# psas_c3_team05.net
KiCad netlist of a schematic drawn in EAGLE
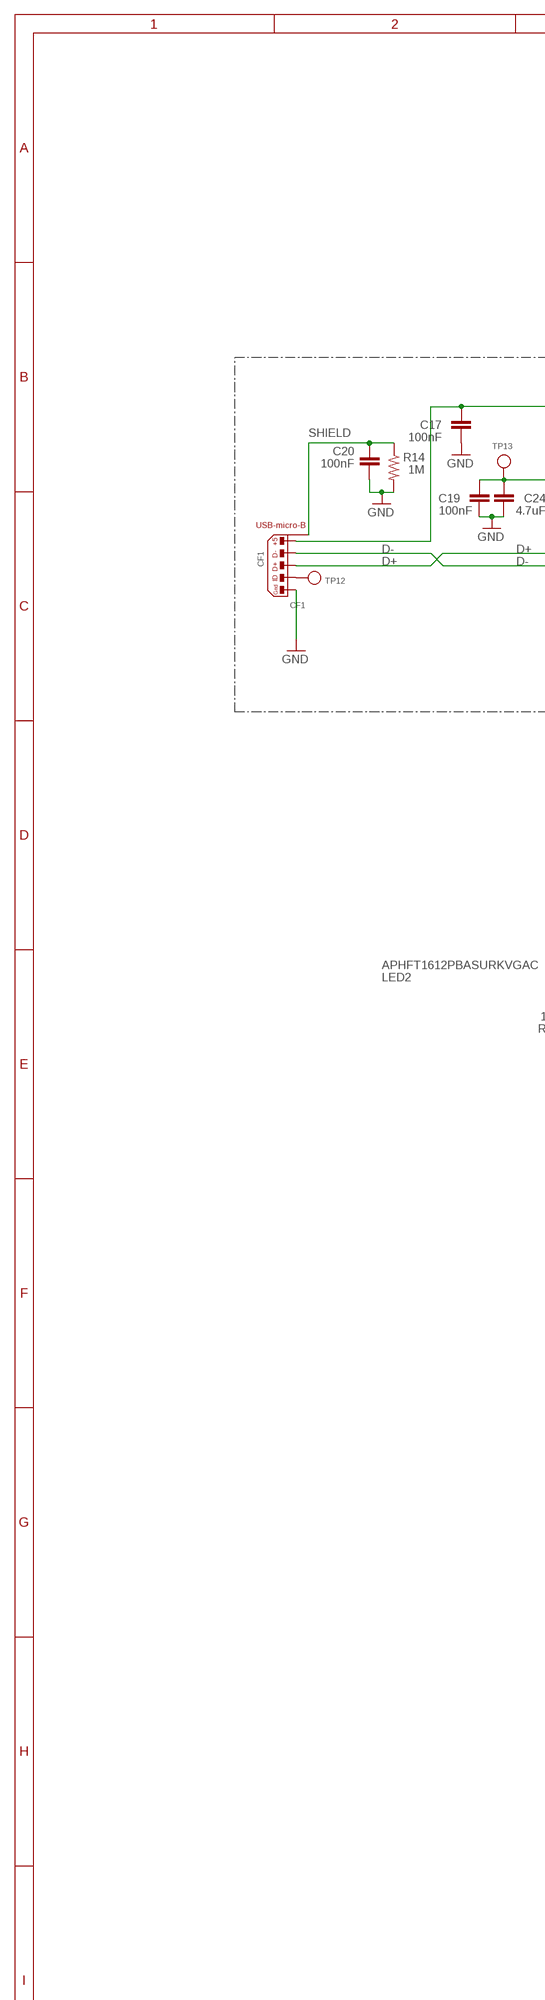
[diagram p0: schematic, sheet 1, part 1 of 2]
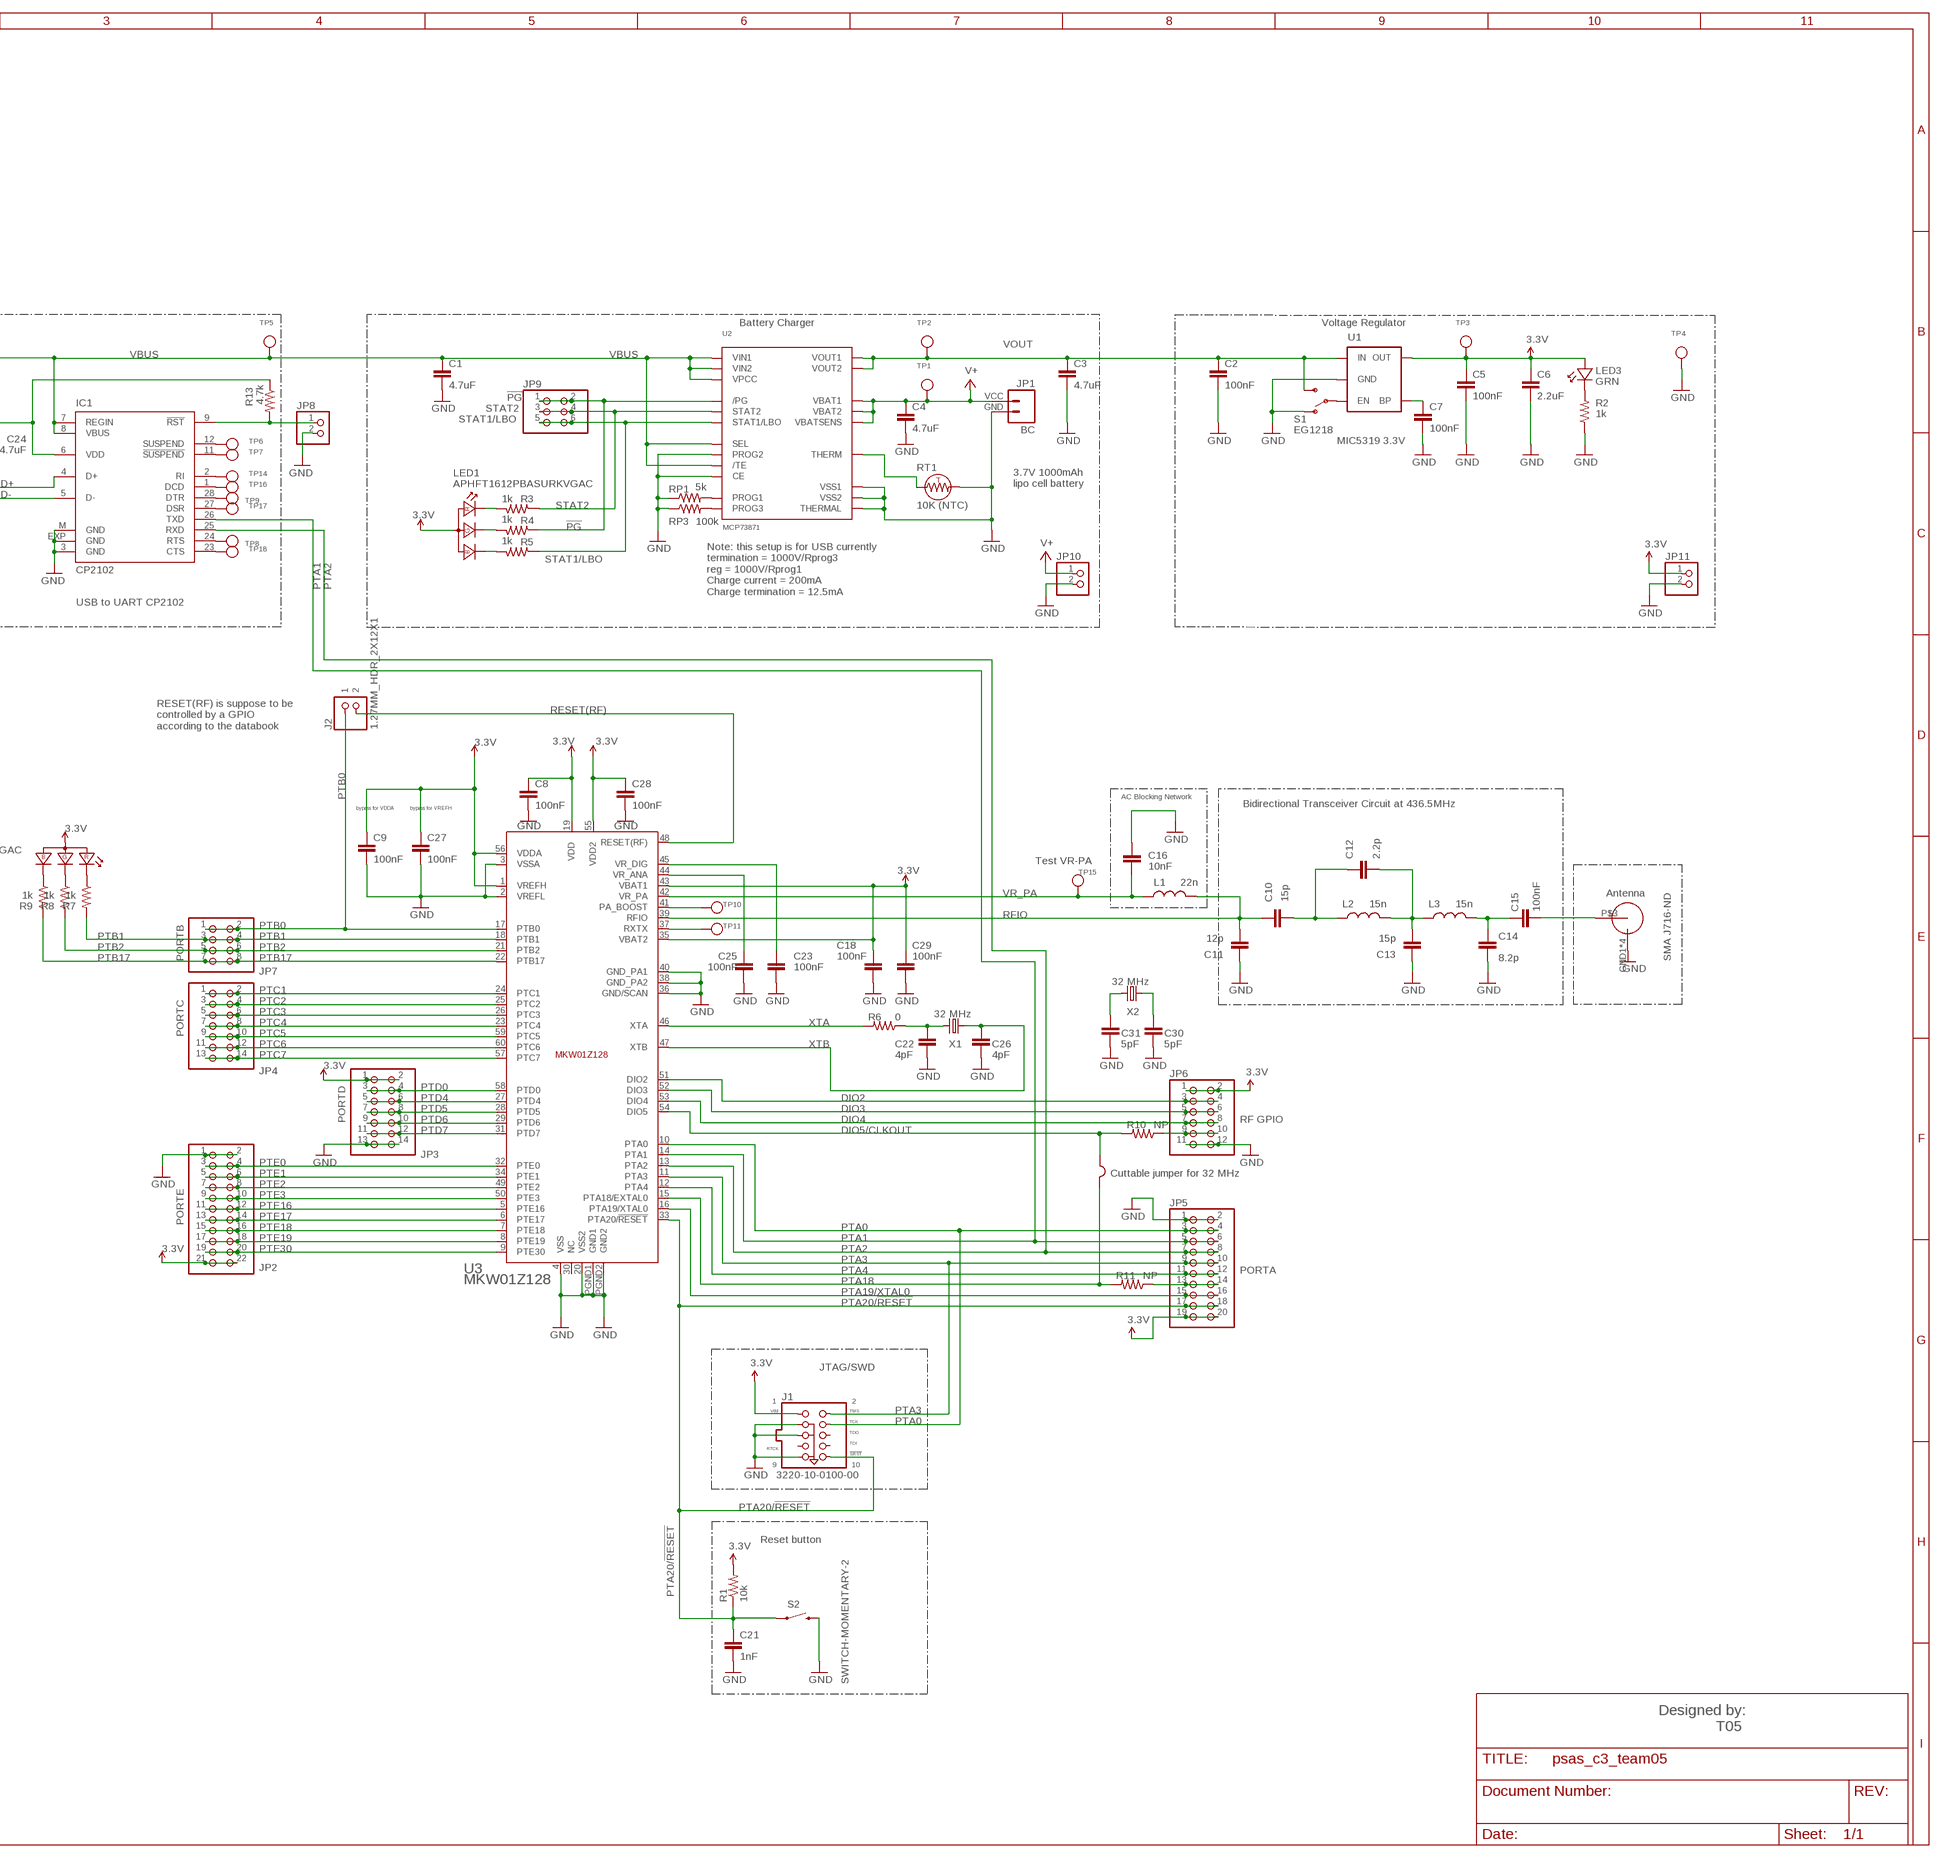
[diagram p1: schematic, sheet 1, part 2 of 2]

(export (version "E")
  (design (tool "Eeschema 10.0.6"))
  (components
    (comp (ref "C1")
      (value "4.7uF")
      (footprint "eagle-import:.0805-B-NOSILK")
      (fields (field (name "MFG") "Wurth Electronics Inc"))
      (libsource (lib "eagle-import") (part "rcl_custom_C-EU0805-B-NOSILK"))
    )
    (comp (ref "C2")
      (value "100nF")
      (footprint "eagle-import:.0603-B-NOSILK")
      (fields (field (name "MFG") "Murata Electronics North America"))
      (libsource (lib "eagle-import") (part "rcl_custom_C-EU0603-B-NOSILK"))
    )
    (comp (ref "C3")
      (value "4.7uF")
      (footprint "eagle-import:.0805-B-NOSILK")
      (fields (field (name "MFG") "Wurth Electronics Inc"))
      (libsource (lib "eagle-import") (part "rcl_custom_C-EU0805-B-NOSILK"))
    )
    (comp (ref "C4")
      (value "4.7uF")
      (footprint "eagle-import:.0805-B-NOSILK")
      (fields (field (name "MFG") "Wurth Electronics Inc"))
      (libsource (lib "eagle-import") (part "rcl_custom_C-EU0805-B-NOSILK"))
    )
    (comp (ref "C5")
      (value "100nF")
      (footprint "eagle-import:.0603-B-NOSILK")
      (fields (field (name "MFG") "Murata Electronics North America"))
      (libsource (lib "eagle-import") (part "rcl_custom_C-EU0603-B-NOSILK"))
    )
    (comp (ref "C6")
      (value "2.2uF")
      (footprint "eagle-import:.0805-B-NOSILK")
      (fields (field (name "MFG") "Murata Electronics North America"))
      (libsource (lib "eagle-import") (part "rcl_custom_C-EU0805-B-NOSILK"))
    )
    (comp (ref "C7")
      (value "100nF")
      (footprint "eagle-import:.0603-B-NOSILK")
      (fields (field (name "MFG") "Murata Electronics North America"))
      (libsource (lib "eagle-import") (part "rcl_custom_C-EU0603-B-NOSILK"))
    )
    (comp (ref "C8")
      (value "100nF")
      (footprint "eagle-import:.0603-B-NOSILK")
      (fields
        (field (name "MFG") "Murata Electronics North America")
        (field (name "MPN") "GRM188R71C104KA01D")
      )
      (libsource (lib "eagle-import") (part "C-EU0603-B-NOSILK"))
    )
    (comp (ref "C9")
      (value "100nF")
      (footprint "eagle-import:.0603-B-NOSILK")
      (fields
        (field (name "MFG") "Murata Electronics North America")
        (field (name "MPN") "GRM188R71C104KA01D")
      )
      (libsource (lib "eagle-import") (part "C-EU0603-B-NOSILK"))
    )
    (comp (ref "C10")
      (value "15p")
      (footprint "eagle-import:.0603-B-NOSILK")
      (fields (field (name "MFG") "AVX"))
      (libsource (lib "eagle-import") (part "rcl_custom_C-EU0603-B-NOSILK"))
    )
    (comp (ref "C11")
      (value "12p")
      (footprint "eagle-import:.0603-B-NOSILK")
      (fields (field (name "MFG") "AVX"))
      (libsource (lib "eagle-import") (part "rcl_custom_C-EU0603-B-NOSILK"))
    )
    (comp (ref "C12")
      (value "2.2p")
      (footprint "eagle-import:.0603-B-NOSILK")
      (fields (field (name "MFG") "Vishay / Vitramon"))
      (libsource (lib "eagle-import") (part "rcl_custom_C-EU0603-B-NOSILK"))
    )
    (comp (ref "C13")
      (value "15p")
      (footprint "eagle-import:.0603-B-NOSILK")
      (fields (field (name "MFG") "AVX"))
      (libsource (lib "eagle-import") (part "rcl_custom_C-EU0603-B-NOSILK"))
    )
    (comp (ref "C14")
      (value "8.2p")
      (footprint "eagle-import:.0603-B-NOSILK")
      (fields (field (name "MFG") "Johanson Technology"))
      (libsource (lib "eagle-import") (part "rcl_custom_C-EU0603-B-NOSILK"))
    )
    (comp (ref "C15")
      (value "100nF")
      (footprint "eagle-import:.0603-B-NOSILK")
      (fields (field (name "MFG") "AVX"))
      (libsource (lib "eagle-import") (part "rcl_custom_C-EU0603-B-NOSILK"))
    )
    (comp (ref "C16")
      (value "10nF")
      (footprint "eagle-import:.0603-B-NOSILK")
      (fields (field (name "MFG") "AVX"))
      (libsource (lib "eagle-import") (part "rcl_custom_C-EU0603-B-NOSILK"))
    )
    (comp (ref "C17")
      (value "100nF")
      (footprint "eagle-import:.0603-B-NOSILK")
      (fields (field (name "MFG") "Murata Electronics North America"))
      (libsource (lib "eagle-import") (part "rcl_custom_C-EU0603-B-NOSILK"))
    )
    (comp (ref "C18")
      (value "100nF")
      (footprint "eagle-import:.0603-B-NOSILK")
      (fields
        (field (name "MFG") "Murata Electronics North America")
        (field (name "MPN") "GRM188R71C104KA01D")
      )
      (libsource (lib "eagle-import") (part "C-EU0603-B-NOSILK"))
    )
    (comp (ref "C19")
      (value "100nF")
      (footprint "eagle-import:.0603-B-NOSILK")
      (fields (field (name "MFG") "Murata Electronics North America"))
      (libsource (lib "eagle-import") (part "rcl_custom_C-EU0603-B-NOSILK"))
    )
    (comp (ref "C20")
      (value "100nF")
      (footprint "eagle-import:.0603-B-NOSILK")
      (fields (field (name "MFG") "Murata Electronics North America"))
      (libsource (lib "eagle-import") (part "rcl_custom_C-EU0603-B-NOSILK"))
    )
    (comp (ref "C21")
      (value "1nF")
      (footprint "eagle-import:.0603-B-NOSILK")
      (fields (field (name "MFG") "Kemet"))
      (libsource (lib "eagle-import") (part "rcl_custom_C-EU0603-B-NOSILK"))
    )
    (comp (ref "C22")
      (value "4pF")
      (footprint "eagle-import:.0603-B-NOSILK")
      (fields
        (field (name "MFG") "Murata Electronics North America")
        (field (name "MPN") "GRM1885C1H4R0CA01D")
      )
      (libsource (lib "eagle-import") (part "C-EU0603-B-NOSILK"))
    )
    (comp (ref "C23")
      (value "100nF")
      (footprint "eagle-import:.0603-B-NOSILK")
      (fields
        (field (name "MFG") "Murata Electronics North America")
        (field (name "MPN") "GRM188R71C104KA01D")
      )
      (libsource (lib "eagle-import") (part "C-EU0603-B-NOSILK"))
    )
    (comp (ref "C24")
      (value "4.7uF")
      (footprint "eagle-import:.0805-B-NOSILK")
      (fields (field (name "MFG") "Wurth Electronics Inc"))
      (libsource (lib "eagle-import") (part "rcl_custom_C-EU0805-B-NOSILK"))
    )
    (comp (ref "C25")
      (value "100nF")
      (footprint "eagle-import:.0603-B-NOSILK")
      (fields
        (field (name "MFG") "Murata Electronics North America")
        (field (name "MPN") "GRM188R71C104KA01D")
      )
      (libsource (lib "eagle-import") (part "C-EU0603-B-NOSILK"))
    )
    (comp (ref "C26")
      (value "4pF")
      (footprint "eagle-import:.0603-B-NOSILK")
      (fields
        (field (name "MFG") "Murata Electronics North America")
        (field (name "MPN") "GRM1885C1H4R0CA01D")
      )
      (libsource (lib "eagle-import") (part "C-EU0603-B-NOSILK"))
    )
    (comp (ref "C27")
      (value "100nF")
      (footprint "eagle-import:.0603-B-NOSILK")
      (fields
        (field (name "MFG") "Murata Electronics North America")
        (field (name "MPN") "GRM188R71C104KA01D")
      )
      (libsource (lib "eagle-import") (part "C-EU0603-B-NOSILK"))
    )
    (comp (ref "C28")
      (value "100nF")
      (footprint "eagle-import:.0603-B-NOSILK")
      (fields
        (field (name "MFG") "Murata Electronics North America")
        (field (name "MPN") "GRM188R71C104KA01D")
      )
      (libsource (lib "eagle-import") (part "C-EU0603-B-NOSILK"))
    )
    (comp (ref "C29")
      (value "100nF")
      (footprint "eagle-import:.0603-B-NOSILK")
      (fields
        (field (name "MFG") "Murata Electronics North America")
        (field (name "MPN") "GRM188R71C104KA01D")
      )
      (libsource (lib "eagle-import") (part "C-EU0603-B-NOSILK"))
    )
    (comp (ref "C30")
      (value "5pF")
      (footprint "eagle-import:.0603-B-NOSILK")
      (fields
        (field (name "MFG") "Murata Electronics North America")
        (field (name "MPN") "GRM1885C1H4R0CA01D")
      )
      (libsource (lib "eagle-import") (part "C-EU0603-B-NOSILK"))
    )
    (comp (ref "C31")
      (value "5pF")
      (footprint "eagle-import:.0603-B-NOSILK")
      (fields
        (field (name "MFG") "Murata Electronics North America")
        (field (name "MPN") "GRM1885C1H4R0CA01D")
      )
      (libsource (lib "eagle-import") (part "C-EU0603-B-NOSILK"))
    )
    (comp (ref "CF1")
      (value "CF1")
      (footprint "eagle-import:USB-MICRO-B-PTH-HIROSE")
      (fields (field (name "MFG") "Hirose Electric Co Ltd"))
      (libsource (lib "eagle-import") (part "CON_USB-MICRO-B-RECEPTACLE-PTH-HIROSE-ZX62D-B-5P8"))
    )
    (comp (ref "IC1")
      (value "CP2102")
      (footprint "eagle-import:MLP28")
      (fields
        (field (name "MF") "FARNELL")
        (field (name "MPN") "CP2102-GM")
        (field (name "MFG") "Silicon Labs")
      )
      (libsource (lib "eagle-import") (part "CP2102"))
    )
    (comp (ref "J1")
      (value "3220-10-0100-00")
      (footprint "eagle-import:PINHEADER-2X5-0.05+POL+SILK")
      (fields (field (name "MFG") "CNC Tech"))
      (libsource (lib "eagle-import") (part "JTAG_ARM-10-50MIL"))
    )
    (comp (ref "J2")
      (value "1.27MM_HDR_2X12X1")
      (footprint "eagle-import:1.27MM_2X1")
      (libsource (lib "eagle-import") (part "1.27MM_HDR_2X12X1"))
    )
    (comp (ref "JP1")
      (value "BC")
      (footprint "eagle-import:SPARKFUN-CONNECTORS_JST-2-SMD-VERT")
      (fields (field (name "MFG") "JST Sales America Inc."))
      (libsource (lib "eagle-import") (part "SPARKFUN-CONNECTORS_M024UCON-15767"))
    )
    (comp (ref "JP2")
      (value "PINHD-2X11")
      (footprint "eagle-import:2X11")
      (libsource (lib "eagle-import") (part "PINHD-2X11"))
    )
    (comp (ref "JP3")
      (value "PINHD-2X7")
      (footprint "eagle-import:2X07")
      (libsource (lib "eagle-import") (part "PINHD-2X7"))
    )
    (comp (ref "JP4")
      (value "PINHD-2X7")
      (footprint "eagle-import:2X07")
      (libsource (lib "eagle-import") (part "PINHD-2X7"))
    )
    (comp (ref "JP5")
      (value "PINHD-2X10")
      (footprint "eagle-import:2X10")
      (libsource (lib "eagle-import") (part "PINHD-2X10"))
    )
    (comp (ref "JP6")
      (value "PINHD-2X6")
      (footprint "eagle-import:2X06")
      (libsource (lib "eagle-import") (part "PINHD-2X6"))
    )
    (comp (ref "JP7")
      (value "PINHD-2X4")
      (footprint "eagle-import:2X04")
      (libsource (lib "eagle-import") (part "PINHD-2X4"))
    )
    (comp (ref "JP8")
      (value "PINHD-1X2")
      (footprint "eagle-import:1X02")
      (libsource (lib "eagle-import") (part "PINHD-1X2"))
    )
    (comp (ref "JP9")
      (value "PINHD-2X3")
      (footprint "eagle-import:2X03")
      (libsource (lib "eagle-import") (part "PINHD-2X3"))
    )
    (comp (ref "JP10")
      (value "PINHD-1X2")
      (footprint "eagle-import:1X02")
      (libsource (lib "eagle-import") (part "PINHD-1X2"))
    )
    (comp (ref "JP11")
      (value "PINHD-1X2")
      (footprint "eagle-import:1X02")
      (libsource (lib "eagle-import") (part "PINHD-1X2"))
    )
    (comp (ref "L1")
      (value "22n")
      (footprint "eagle-import:.0603-B-NOSILK")
      (fields (field (name "MFG") "Murata"))
      (libsource (lib "eagle-import") (part "L-US0603-B-NOSILK"))
    )
    (comp (ref "L2")
      (value "15n")
      (footprint "eagle-import:.0603-B-NOSILK")
      (fields (field (name "MFG") "Murata"))
      (libsource (lib "eagle-import") (part "L-US0603-B-NOSILK"))
    )
    (comp (ref "L3")
      (value "15n")
      (footprint "eagle-import:.0603-B-NOSILK")
      (fields (field (name "MFG") "Murata"))
      (libsource (lib "eagle-import") (part "L-US0603-B-NOSILK"))
    )
    (comp (ref "LED1")
      (value "APHFT1612PBASURKVGAC")
      (footprint "eagle-import:KINGBRITE_RGBLED_1.6X1.26")
      (fields (field (name "MFG") "Lite-On Inc."))
      (libsource (lib "eagle-import") (part "LED_RGB_COMMON_ANODE-1.6X1.26"))
    )
    (comp (ref "LED2")
      (value "APHFT1612PBASURKVGAC")
      (footprint "eagle-import:KINGBRITE_RGBLED_1.6X1.26")
      (fields (field (name "MFG") "Lite-On Inc."))
      (libsource (lib "eagle-import") (part "LED_RGB_COMMON_ANODE-1.6X1.26"))
    )
    (comp (ref "LED3")
      (value "GRN")
      (footprint "eagle-import:LED-0603")
      (fields (field (name "MFG") "Lite-On Inc."))
      (libsource (lib "eagle-import") (part "LED-0603"))
    )
    (comp (ref "R1")
      (value "10k")
      (footprint "eagle-import:.0603-B-NOSILK")
      (fields (field (name "MFG") "Yageo"))
      (libsource (lib "eagle-import") (part "R-US_0603-B-NOSILK"))
    )
    (comp (ref "R2")
      (value "1k")
      (footprint "eagle-import:.0603-B-NOSILK")
      (fields (field (name "MFG") "Yageo"))
      (libsource (lib "eagle-import") (part "R-US_0603-B-NOSILK"))
    )
    (comp (ref "R3")
      (value "1k")
      (footprint "eagle-import:.0603-B-NOSILK")
      (fields (field (name "MFG") "Yageo"))
      (libsource (lib "eagle-import") (part "R-US_0603-B-NOSILK"))
    )
    (comp (ref "R4")
      (value "1k")
      (footprint "eagle-import:.0603-B-NOSILK")
      (fields (field (name "MFG") "Yageo"))
      (libsource (lib "eagle-import") (part "R-US_0603-B-NOSILK"))
    )
    (comp (ref "R5")
      (value "1k")
      (footprint "eagle-import:.0603-B-NOSILK")
      (fields (field (name "MFG") "Yageo"))
      (libsource (lib "eagle-import") (part "R-US_0603-B-NOSILK"))
    )
    (comp (ref "R6")
      (value "0")
      (footprint "eagle-import:.0603-B-NOSILK")
      (libsource (lib "eagle-import") (part "R-US_0603-B-NOSILK"))
    )
    (comp (ref "R7")
      (value "1k")
      (footprint "eagle-import:.0603-B-NOSILK")
      (fields (field (name "MFG") "Yageo"))
      (libsource (lib "eagle-import") (part "R-US_0603-B-NOSILK"))
    )
    (comp (ref "R8")
      (value "1k")
      (footprint "eagle-import:.0603-B-NOSILK")
      (fields (field (name "MFG") "Yageo"))
      (libsource (lib "eagle-import") (part "R-US_0603-B-NOSILK"))
    )
    (comp (ref "R9")
      (value "1k")
      (footprint "eagle-import:.0603-B-NOSILK")
      (fields (field (name "MFG") "Yageo"))
      (libsource (lib "eagle-import") (part "R-US_0603-B-NOSILK"))
    )
    (comp (ref "R10")
      (value "NP")
      (footprint "eagle-import:.0603-B-NOSILK")
      (libsource (lib "eagle-import") (part "R-US_0603-B-NOSILK"))
    )
    (comp (ref "R11")
      (value "NP")
      (footprint "eagle-import:.0603-B-NOSILK")
      (libsource (lib "eagle-import") (part "R-US_0603-B-NOSILK"))
    )
    (comp (ref "R13")
      (value "4.7k")
      (footprint "eagle-import:.0603-B-NOSILK")
      (fields (field (name "MFG") "Yageo"))
      (libsource (lib "eagle-import") (part "R-US_0603-B-NOSILK"))
    )
    (comp (ref "R14")
      (value "1M")
      (footprint "eagle-import:.0603-B-NOSILK")
      (fields (field (name "MFG") "Yageo"))
      (libsource (lib "eagle-import") (part "R-US_0603-B-NOSILK"))
    )
    (comp (ref "RP1")
      (value "5k")
      (footprint "eagle-import:.0603-B-NOSILK")
      (fields (field (name "MFG") "Yageo"))
      (libsource (lib "eagle-import") (part "R-US_0603-B-NOSILK"))
    )
    (comp (ref "RP3")
      (value "100k")
      (footprint "eagle-import:.0603-B-NOSILK")
      (fields (field (name "MFG") "Yageo"))
      (libsource (lib "eagle-import") (part "R-US_0603-B-NOSILK"))
    )
    (comp (ref "RT1")
      (value "10K (NTC)")
      (footprint "eagle-import:R1206")
      (fields (field (name "MFG") "Honeywell Sensing and Control"))
      (libsource (lib "eagle-import") (part "THERMISTOR-_1206"))
    )
    (comp (ref "S1")
      (value "EG1218")
      (footprint "eagle-import:SWITCH-SPDT")
      (fields (field (name "MFG") "E-Switch"))
      (libsource (lib "eagle-import") (part "SWITCH-SPSTPTH"))
    )
    (comp (ref "S2")
      (value "SWITCH-MOMENTARY-2")
      (footprint "eagle-import:TACTILE_SWITCH_TALL")
      (fields (field (name "MFG") "TE Connectivity Alcoswitch Switches"))
      (libsource (lib "eagle-import") (part "SWITCH-MOMENTARY-2"))
    )
    (comp (ref "TP1")
      (value "TESTPOINTROUND0.5MM")
      (footprint "eagle-import:TESTPOINT_ROUND_0.5MM")
      (libsource (lib "eagle-import") (part "TESTPOINTROUND0.5MM"))
    )
    (comp (ref "TP2")
      (value "TESTPOINTROUND0.5MM")
      (footprint "eagle-import:TESTPOINT_ROUND_0.5MM")
      (libsource (lib "eagle-import") (part "TESTPOINTROUND0.5MM"))
    )
    (comp (ref "TP3")
      (value "TESTPOINTROUND0.5MM")
      (footprint "eagle-import:TESTPOINT_ROUND_0.5MM")
      (libsource (lib "eagle-import") (part "TESTPOINTROUND0.5MM"))
    )
    (comp (ref "TP4")
      (value "TESTPOINTROUND0.5MM")
      (footprint "eagle-import:TESTPOINT_ROUND_0.5MM")
      (libsource (lib "eagle-import") (part "TESTPOINTROUND0.5MM"))
    )
    (comp (ref "TP5")
      (value "TESTPOINTROUND0.5MM")
      (footprint "eagle-import:TESTPOINT_ROUND_0.5MM")
      (libsource (lib "eagle-import") (part "TESTPOINTROUND0.5MM"))
    )
    (comp (ref "TP6")
      (value "TESTPOINTROUND0.5MM")
      (footprint "eagle-import:TESTPOINT_ROUND_0.5MM")
      (libsource (lib "eagle-import") (part "TESTPOINTROUND0.5MM"))
    )
    (comp (ref "TP7")
      (value "TESTPOINTROUND0.5MM")
      (footprint "eagle-import:TESTPOINT_ROUND_0.5MM")
      (libsource (lib "eagle-import") (part "TESTPOINTROUND0.5MM"))
    )
    (comp (ref "TP8")
      (value "TESTPOINTROUND0.5MM")
      (footprint "eagle-import:TESTPOINT_ROUND_0.5MM")
      (libsource (lib "eagle-import") (part "TESTPOINTROUND0.5MM"))
    )
    (comp (ref "TP9")
      (value "TESTPOINTROUND0.5MM")
      (footprint "eagle-import:TESTPOINT_ROUND_0.5MM")
      (libsource (lib "eagle-import") (part "TESTPOINTROUND0.5MM"))
    )
    (comp (ref "TP10")
      (value "TESTPOINTROUND0.5MM")
      (footprint "eagle-import:TESTPOINT_ROUND_0.5MM")
      (libsource (lib "eagle-import") (part "TESTPOINTROUND0.5MM"))
    )
    (comp (ref "TP11")
      (value "TESTPOINTROUND0.5MM")
      (footprint "eagle-import:TESTPOINT_ROUND_0.5MM")
      (libsource (lib "eagle-import") (part "TESTPOINTROUND0.5MM"))
    )
    (comp (ref "TP12")
      (value "TESTPOINTROUND0.5MM")
      (footprint "eagle-import:TESTPOINT_ROUND_0.5MM")
      (libsource (lib "eagle-import") (part "TESTPOINTROUND0.5MM"))
    )
    (comp (ref "TP13")
      (value "TESTPOINTROUND0.5MM")
      (footprint "eagle-import:TESTPOINT_ROUND_0.5MM")
      (libsource (lib "eagle-import") (part "TESTPOINTROUND0.5MM"))
    )
    (comp (ref "TP14")
      (value "TESTPOINTROUND0.5MM")
      (footprint "eagle-import:TESTPOINT_ROUND_0.5MM")
      (libsource (lib "eagle-import") (part "TESTPOINTROUND0.5MM"))
    )
    (comp (ref "TP15")
      (value "TESTPOINTROUND0.5MM")
      (footprint "eagle-import:TESTPOINT_ROUND_0.5MM")
      (libsource (lib "eagle-import") (part "TESTPOINTROUND0.5MM"))
    )
    (comp (ref "TP16")
      (value "TESTPOINTROUND0.5MM")
      (footprint "eagle-import:TESTPOINT_ROUND_0.5MM")
      (libsource (lib "eagle-import") (part "TESTPOINTROUND0.5MM"))
    )
    (comp (ref "TP17")
      (value "TESTPOINTROUND0.5MM")
      (footprint "eagle-import:TESTPOINT_ROUND_0.5MM")
      (libsource (lib "eagle-import") (part "TESTPOINTROUND0.5MM"))
    )
    (comp (ref "TP18")
      (value "TESTPOINTROUND0.5MM")
      (footprint "eagle-import:TESTPOINT_ROUND_0.5MM")
      (libsource (lib "eagle-import") (part "TESTPOINTROUND0.5MM"))
    )
    (comp (ref "U$2")
      (value "SMAJ716-ND")
      (footprint "eagle-import:SMAJ716-ND")
      (fields (field (name "MFG") "Cinch Connectivity Solutions"))
      (libsource (lib "eagle-import") (part "SMAJ716-ND"))
    )
    (comp (ref "U1")
      (value "MIC5319 3.3V")
      (footprint "eagle-import:SPARKFUN-POWERIC_SOT23-5")
      (fields (field (name "MFG") "Microchip Technology"))
      (libsource (lib "eagle-import") (part "SPARKFUN-POWERIC_V_REG_MIC52193.3V"))
    )
    (comp (ref "U2")
      (value "MCP73871")
      (footprint "eagle-import:QFN20_4MM")
      (fields (field (name "MFG") "Microchip Technology"))
      (libsource (lib "eagle-import") (part "MCP73871"))
    )
    (comp (ref "U3")
      (value "MKW01Z128")
      (footprint "eagle-import:MKW01Z128")
      (fields (field (name "MFG") "Freescale Semiconductor"))
      (libsource (lib "eagle-import") (part "MKW01Z128"))
    )
    (comp (ref "W1")
      (value "CONNECTION-0.4")
      (footprint "eagle-import:CONNECTION-BUTT-0.4")
      (libsource (lib "eagle-import") (part "CONNECTION-0.4"))
    )
    (comp (ref "X1")
      (value "32 MHz")
      (footprint "eagle-import:FC-12M")
      (fields (field (name "MFG") "AVX Corp/Kyocera Corp"))
      (libsource (lib "eagle-import") (part "FC-12M"))
    )
    (comp (ref "X2")
      (value "32 MHz")
      (footprint "eagle-import:FC-12M")
      (fields (field (name "MFG") "CTS-Frequency Controls"))
      (libsource (lib "eagle-import") (part "FC-12M"))
    )
  )
  (nets
    (net (code "1") (name "/D+") (class "Default")
      (node (ref "CF1") (pin "3") (pinfunction "3_3") (pintype "passive"))
      (node (ref "IC1") (pin "4") (pinfunction "D+_4") (pintype "bidirectional"))
    )
    (net (code "2") (name "/D-") (class "Default")
      (node (ref "CF1") (pin "2") (pinfunction "2_2") (pintype "passive"))
      (node (ref "IC1") (pin "5") (pinfunction "D-_5") (pintype "bidirectional"))
    )
    (net (code "3") (name "/DIO2") (class "Default")
      (node (ref "JP6") (pin "3") (pinfunction "3_3") (pintype "passive"))
      (node (ref "JP6") (pin "4") (pinfunction "4_4") (pintype "passive"))
      (node (ref "U3") (pin "51") (pinfunction "DIO2_51") (pintype "bidirectional"))
    )
    (net (code "4") (name "/DIO3") (class "Default")
      (node (ref "JP6") (pin "5") (pinfunction "5_5") (pintype "passive"))
      (node (ref "JP6") (pin "6") (pinfunction "6_6") (pintype "passive"))
      (node (ref "U3") (pin "52") (pinfunction "DIO3_52") (pintype "bidirectional"))
    )
    (net (code "5") (name "/DIO4") (class "Default")
      (node (ref "JP6") (pin "7") (pinfunction "7_7") (pintype "passive"))
      (node (ref "JP6") (pin "8") (pinfunction "8_8") (pintype "passive"))
      (node (ref "U3") (pin "53") (pinfunction "DIO4_53") (pintype "bidirectional"))
    )
    (net (code "6") (name "/DIO5{slash}CLKOUT") (class "Default")
      (node (ref "R10") (pin "2") (pinfunction "2_2") (pintype "passive"))
      (node (ref "U3") (pin "54") (pinfunction "DIO5_54") (pintype "bidirectional"))
      (node (ref "W1") (pin "P1") (pinfunction "1_P1") (pintype "passive"))
    )
    (net (code "7") (name "/PTA0") (class "Default")
      (node (ref "J1") (pin "4") (pinfunction "TCK_4") (pintype "passive"))
      (node (ref "JP5") (pin "3") (pinfunction "3_3") (pintype "passive"))
      (node (ref "JP5") (pin "4") (pinfunction "4_4") (pintype "passive"))
      (node (ref "U3") (pin "10") (pinfunction "PTA0_10") (pintype "bidirectional"))
    )
    (net (code "8") (name "/PTA1") (class "Default")
      (node (ref "IC1") (pin "26") (pinfunction "TXD_26") (pintype "output"))
      (node (ref "JP5") (pin "5") (pinfunction "5_5") (pintype "passive"))
      (node (ref "JP5") (pin "6") (pinfunction "6_6") (pintype "passive"))
      (node (ref "U3") (pin "14") (pinfunction "PTA1_14") (pintype "bidirectional"))
    )
    (net (code "9") (name "/PTA2") (class "Default")
      (node (ref "IC1") (pin "25") (pinfunction "RXD_25") (pintype "input"))
      (node (ref "JP5") (pin "7") (pinfunction "7_7") (pintype "passive"))
      (node (ref "JP5") (pin "8") (pinfunction "8_8") (pintype "passive"))
      (node (ref "U3") (pin "13") (pinfunction "PTA2_13") (pintype "bidirectional"))
    )
    (net (code "10") (name "/PTA3") (class "Default")
      (node (ref "J1") (pin "2") (pinfunction "TMS_2") (pintype "passive"))
      (node (ref "JP5") (pin "10") (pinfunction "10_10") (pintype "passive"))
      (node (ref "JP5") (pin "9") (pinfunction "9_9") (pintype "passive"))
      (node (ref "U3") (pin "11") (pinfunction "PTA3_11") (pintype "bidirectional"))
    )
    (net (code "11") (name "/PTA4") (class "Default")
      (node (ref "JP5") (pin "11") (pinfunction "11_11") (pintype "passive"))
      (node (ref "JP5") (pin "12") (pinfunction "12_12") (pintype "passive"))
      (node (ref "U3") (pin "12") (pinfunction "PTA4_12") (pintype "bidirectional"))
    )
    (net (code "12") (name "/PTA18") (class "Default")
      (node (ref "R11") (pin "2") (pinfunction "2_2") (pintype "passive"))
      (node (ref "U3") (pin "15") (pinfunction "PTA18/EXTAL0_15") (pintype "bidirectional"))
      (node (ref "W1") (pin "P2") (pinfunction "2_P2") (pintype "passive"))
    )
    (net (code "13") (name "/PTA19{slash}XTAL0") (class "Default")
      (node (ref "JP5") (pin "15") (pinfunction "15_15") (pintype "passive"))
      (node (ref "JP5") (pin "16") (pinfunction "16_16") (pintype "passive"))
      (node (ref "U3") (pin "16") (pinfunction "PTA19/XTAL0_16") (pintype "bidirectional"))
    )
    (net (code "14") (name "/PTA20{slash}~{RESET}") (class "Default")
      (node (ref "C21") (pin "1") (pinfunction "1_1") (pintype "passive"))
      (node (ref "J1") (pin "10") (pinfunction "SRST_10") (pintype "passive"))
      (node (ref "JP5") (pin "17") (pinfunction "17_17") (pintype "passive"))
      (node (ref "JP5") (pin "18") (pinfunction "18_18") (pintype "passive"))
      (node (ref "R1") (pin "1") (pinfunction "1_1") (pintype "passive"))
      (node (ref "S2") (pin "A2") (pinfunction "1_A2") (pintype "passive"))
      (node (ref "U3") (pin "33") (pinfunction "PTA20/~{RESET}_33") (pintype "bidirectional"))
    )
    (net (code "15") (name "/PTB0") (class "Default")
      (node (ref "J2") (pin "1") (pinfunction "1_1") (pintype "passive"))
      (node (ref "JP7") (pin "1") (pinfunction "1_1") (pintype "passive"))
      (node (ref "JP7") (pin "2") (pinfunction "2_2") (pintype "passive"))
      (node (ref "U3") (pin "17") (pinfunction "PTB0_17") (pintype "bidirectional"))
    )
    (net (code "16") (name "/PTB1") (class "Default")
      (node (ref "JP7") (pin "3") (pinfunction "3_3") (pintype "passive"))
      (node (ref "JP7") (pin "4") (pinfunction "4_4") (pintype "passive"))
      (node (ref "R7") (pin "2") (pinfunction "2_2") (pintype "passive"))
      (node (ref "U3") (pin "18") (pinfunction "PTB1_18") (pintype "bidirectional"))
    )
    (net (code "17") (name "/PTB2") (class "Default")
      (node (ref "JP7") (pin "5") (pinfunction "5_5") (pintype "passive"))
      (node (ref "JP7") (pin "6") (pinfunction "6_6") (pintype "passive"))
      (node (ref "R8") (pin "2") (pinfunction "2_2") (pintype "passive"))
      (node (ref "U3") (pin "21") (pinfunction "PTB2_21") (pintype "bidirectional"))
    )
    (net (code "18") (name "/PTB17") (class "Default")
      (node (ref "JP7") (pin "7") (pinfunction "7_7") (pintype "passive"))
      (node (ref "JP7") (pin "8") (pinfunction "8_8") (pintype "passive"))
      (node (ref "R9") (pin "2") (pinfunction "2_2") (pintype "passive"))
      (node (ref "U3") (pin "22") (pinfunction "PTB17_22") (pintype "bidirectional"))
    )
    (net (code "19") (name "/PTC1") (class "Default")
      (node (ref "JP4") (pin "1") (pinfunction "1_1") (pintype "passive"))
      (node (ref "JP4") (pin "2") (pinfunction "2_2") (pintype "passive"))
      (node (ref "U3") (pin "24") (pinfunction "PTC1_24") (pintype "bidirectional"))
    )
    (net (code "20") (name "/PTC2") (class "Default")
      (node (ref "JP4") (pin "3") (pinfunction "3_3") (pintype "passive"))
      (node (ref "JP4") (pin "4") (pinfunction "4_4") (pintype "passive"))
      (node (ref "U3") (pin "25") (pinfunction "PTC2_25") (pintype "bidirectional"))
    )
    (net (code "21") (name "/PTC3") (class "Default")
      (node (ref "JP4") (pin "5") (pinfunction "5_5") (pintype "passive"))
      (node (ref "JP4") (pin "6") (pinfunction "6_6") (pintype "passive"))
      (node (ref "U3") (pin "26") (pinfunction "PTC3_26") (pintype "bidirectional"))
    )
    (net (code "22") (name "/PTC4") (class "Default")
      (node (ref "JP4") (pin "7") (pinfunction "7_7") (pintype "passive"))
      (node (ref "JP4") (pin "8") (pinfunction "8_8") (pintype "passive"))
      (node (ref "U3") (pin "23") (pinfunction "PTC4_23") (pintype "bidirectional"))
    )
    (net (code "23") (name "/PTC5") (class "Default")
      (node (ref "JP4") (pin "10") (pinfunction "10_10") (pintype "passive"))
      (node (ref "JP4") (pin "9") (pinfunction "9_9") (pintype "passive"))
      (node (ref "U3") (pin "59") (pinfunction "PTC5_59") (pintype "bidirectional"))
    )
    (net (code "24") (name "/PTC6") (class "Default")
      (node (ref "JP4") (pin "11") (pinfunction "11_11") (pintype "passive"))
      (node (ref "JP4") (pin "12") (pinfunction "12_12") (pintype "passive"))
      (node (ref "U3") (pin "60") (pinfunction "PTC6_60") (pintype "bidirectional"))
    )
    (net (code "25") (name "/PTC7") (class "Default")
      (node (ref "JP4") (pin "13") (pinfunction "13_13") (pintype "passive"))
      (node (ref "JP4") (pin "14") (pinfunction "14_14") (pintype "passive"))
      (node (ref "U3") (pin "57") (pinfunction "PTC7_57") (pintype "bidirectional"))
    )
    (net (code "26") (name "/PTD0") (class "Default")
      (node (ref "JP3") (pin "3") (pinfunction "3_3") (pintype "passive"))
      (node (ref "JP3") (pin "4") (pinfunction "4_4") (pintype "passive"))
      (node (ref "U3") (pin "58") (pinfunction "PTD0_58") (pintype "bidirectional"))
    )
    (net (code "27") (name "/PTD4") (class "Default")
      (node (ref "JP3") (pin "5") (pinfunction "5_5") (pintype "passive"))
      (node (ref "JP3") (pin "6") (pinfunction "6_6") (pintype "passive"))
      (node (ref "U3") (pin "27") (pinfunction "PTD4_27") (pintype "bidirectional"))
    )
    (net (code "28") (name "/PTD5") (class "Default")
      (node (ref "JP3") (pin "7") (pinfunction "7_7") (pintype "passive"))
      (node (ref "JP3") (pin "8") (pinfunction "8_8") (pintype "passive"))
      (node (ref "U3") (pin "28") (pinfunction "PTD5_28") (pintype "bidirectional"))
    )
    (net (code "29") (name "/PTD6") (class "Default")
      (node (ref "JP3") (pin "10") (pinfunction "10_10") (pintype "passive"))
      (node (ref "JP3") (pin "9") (pinfunction "9_9") (pintype "passive"))
      (node (ref "U3") (pin "29") (pinfunction "PTD6_29") (pintype "bidirectional"))
    )
    (net (code "30") (name "/PTD7") (class "Default")
      (node (ref "JP3") (pin "11") (pinfunction "11_11") (pintype "passive"))
      (node (ref "JP3") (pin "12") (pinfunction "12_12") (pintype "passive"))
      (node (ref "U3") (pin "31") (pinfunction "PTD7_31") (pintype "bidirectional"))
    )
    (net (code "31") (name "/PTE0") (class "Default")
      (node (ref "JP2") (pin "3") (pinfunction "3_3") (pintype "passive"))
      (node (ref "JP2") (pin "4") (pinfunction "4_4") (pintype "passive"))
      (node (ref "U3") (pin "32") (pinfunction "PTE0_32") (pintype "bidirectional"))
    )
    (net (code "32") (name "/PTE1") (class "Default")
      (node (ref "JP2") (pin "5") (pinfunction "5_5") (pintype "passive"))
      (node (ref "JP2") (pin "6") (pinfunction "6_6") (pintype "passive"))
      (node (ref "U3") (pin "34") (pinfunction "PTE1_34") (pintype "bidirectional"))
    )
    (net (code "33") (name "/PTE2") (class "Default")
      (node (ref "JP2") (pin "7") (pinfunction "7_7") (pintype "passive"))
      (node (ref "JP2") (pin "8") (pinfunction "8_8") (pintype "passive"))
      (node (ref "U3") (pin "49") (pinfunction "PTE2_49") (pintype "bidirectional"))
    )
    (net (code "34") (name "/PTE3") (class "Default")
      (node (ref "JP2") (pin "10") (pinfunction "10_10") (pintype "passive"))
      (node (ref "JP2") (pin "9") (pinfunction "9_9") (pintype "passive"))
      (node (ref "U3") (pin "50") (pinfunction "PTE3_50") (pintype "bidirectional"))
    )
    (net (code "35") (name "/PTE16") (class "Default")
      (node (ref "JP2") (pin "11") (pinfunction "11_11") (pintype "passive"))
      (node (ref "JP2") (pin "12") (pinfunction "12_12") (pintype "passive"))
      (node (ref "U3") (pin "5") (pinfunction "PTE16_5") (pintype "bidirectional"))
    )
    (net (code "36") (name "/PTE17") (class "Default")
      (node (ref "JP2") (pin "13") (pinfunction "13_13") (pintype "passive"))
      (node (ref "JP2") (pin "14") (pinfunction "14_14") (pintype "passive"))
      (node (ref "U3") (pin "6") (pinfunction "PTE17_6") (pintype "bidirectional"))
    )
    (net (code "37") (name "/PTE18") (class "Default")
      (node (ref "JP2") (pin "15") (pinfunction "15_15") (pintype "passive"))
      (node (ref "JP2") (pin "16") (pinfunction "16_16") (pintype "passive"))
      (node (ref "U3") (pin "7") (pinfunction "PTE18_7") (pintype "bidirectional"))
    )
    (net (code "38") (name "/PTE19") (class "Default")
      (node (ref "JP2") (pin "17") (pinfunction "17_17") (pintype "passive"))
      (node (ref "JP2") (pin "18") (pinfunction "18_18") (pintype "passive"))
      (node (ref "U3") (pin "8") (pinfunction "PTE19_8") (pintype "bidirectional"))
    )
    (net (code "39") (name "/PTE30") (class "Default")
      (node (ref "JP2") (pin "19") (pinfunction "19_19") (pintype "passive"))
      (node (ref "JP2") (pin "20") (pinfunction "20_20") (pintype "passive"))
      (node (ref "U3") (pin "9") (pinfunction "PTE30_9") (pintype "bidirectional"))
    )
    (net (code "40") (name "/RESET(RF)") (class "Default")
      (node (ref "J2") (pin "2") (pinfunction "2_2") (pintype "passive"))
      (node (ref "U3") (pin "48") (pinfunction "RESET(RF)_48") (pintype "input"))
    )
    (net (code "41") (name "/RFIO") (class "Default")
      (node (ref "C10") (pin "2") (pinfunction "2_2") (pintype "passive"))
      (node (ref "C11") (pin "1") (pinfunction "1_1") (pintype "passive"))
      (node (ref "L1") (pin "2") (pinfunction "2_2") (pintype "passive"))
      (node (ref "U3") (pin "39") (pinfunction "RFIO_39") (pintype "bidirectional"))
    )
    (net (code "42") (name "/SHIELD") (class "Default")
      (node (ref "C20") (pin "1") (pinfunction "1_1") (pintype "passive"))
      (node (ref "CF1") (pin "S1") (pinfunction "SHIELD_S1") (pintype "passive"))
      (node (ref "CF1") (pin "S2") (pinfunction "SHIELD_S2") (pintype "passive"))
      (node (ref "CF1") (pin "S3") (pinfunction "SHIELD_S3") (pintype "passive"))
      (node (ref "CF1") (pin "S4") (pinfunction "SHIELD_S4") (pintype "passive"))
      (node (ref "R14") (pin "1") (pinfunction "1_1") (pintype "passive"))
    )
    (net (code "43") (name "/STAT1{slash}LBO") (class "Default")
      (node (ref "JP9") (pin "5") (pinfunction "5_5") (pintype "passive"))
      (node (ref "JP9") (pin "6") (pinfunction "6_6") (pintype "passive"))
      (node (ref "R5") (pin "1") (pinfunction "1_1") (pintype "passive"))
      (node (ref "U2") (pin "P$8") (pinfunction "STAT1/LBO_P$8") (pintype "output"))
    )
    (net (code "44") (name "/STAT2") (class "Default")
      (node (ref "JP9") (pin "3") (pinfunction "3_3") (pintype "passive"))
      (node (ref "JP9") (pin "4") (pinfunction "4_4") (pintype "passive"))
      (node (ref "R3") (pin "1") (pinfunction "1_1") (pintype "passive"))
      (node (ref "U2") (pin "P$7") (pinfunction "STAT2_P$7") (pintype "output"))
    )
    (net (code "45") (name "/VBUS") (class "Default")
      (node (ref "C1") (pin "1") (pinfunction "1_1") (pintype "passive"))
      (node (ref "C17") (pin "1") (pinfunction "1_1") (pintype "passive"))
      (node (ref "CF1") (pin "1") (pinfunction "1_1") (pintype "passive"))
      (node (ref "IC1") (pin "7") (pinfunction "REGIN_7") (pintype "passive"))
      (node (ref "IC1") (pin "8") (pinfunction "VBUS_8") (pintype "input"))
      (node (ref "TP5") (pin "P$1") (pinfunction "P$1_P$1") (pintype "bidirectional"))
      (node (ref "U2") (pin "P$18") (pinfunction "VIN1_P$18") (pintype "power_in"))
      (node (ref "U2") (pin "P$19") (pinfunction "VIN2_P$19") (pintype "power_in"))
      (node (ref "U2") (pin "P$2") (pinfunction "VPCC_P$2") (pintype "passive"))
      (node (ref "U2") (pin "P$3") (pinfunction "SEL_P$3") (pintype "input"))
      (node (ref "U2") (pin "P$9") (pinfunction "/TE_P$9") (pintype "input"))
    )
    (net (code "46") (name "/VOUT") (class "Default")
      (node (ref "C2") (pin "1") (pinfunction "1_1") (pintype "passive"))
      (node (ref "C3") (pin "1") (pinfunction "1_1") (pintype "passive"))
      (node (ref "S1") (pin "3") (pinfunction "S_3") (pintype "passive"))
      (node (ref "TP2") (pin "P$1") (pinfunction "P$1_P$1") (pintype "bidirectional"))
      (node (ref "U1") (pin "1") (pinfunction "IN_1") (pintype "input"))
      (node (ref "U2") (pin "P$1") (pinfunction "VOUT1_P$1") (pintype "power_in"))
      (node (ref "U2") (pin "P$20") (pinfunction "VOUT2_P$20") (pintype "power_in"))
    )
    (net (code "47") (name "/VR_PA") (class "Default")
      (node (ref "C16") (pin "2") (pinfunction "2_2") (pintype "passive"))
      (node (ref "L1") (pin "1") (pinfunction "1_1") (pintype "passive"))
      (node (ref "TP15") (pin "P$1") (pinfunction "P$1_P$1") (pintype "bidirectional"))
      (node (ref "U3") (pin "42") (pinfunction "VR_PA_42") (pintype "output"))
    )
    (net (code "48") (name "/XTA") (class "Default")
      (node (ref "R6") (pin "2") (pinfunction "2_2") (pintype "passive"))
      (node (ref "U3") (pin "46") (pinfunction "XTA_46") (pintype "passive"))
    )
    (net (code "49") (name "/XTB") (class "Default")
      (node (ref "C26") (pin "1") (pinfunction "1_1") (pintype "passive"))
      (node (ref "U3") (pin "47") (pinfunction "XTB_47") (pintype "passive"))
      (node (ref "X1") (pin "1") (pinfunction "1_1") (pintype "passive"))
    )
    (net (code "50") (name "/~{PG}") (class "Default")
      (node (ref "JP9") (pin "1") (pinfunction "1_1") (pintype "passive"))
      (node (ref "JP9") (pin "2") (pinfunction "2_2") (pintype "passive"))
      (node (ref "R4") (pin "1") (pinfunction "1_1") (pintype "passive"))
      (node (ref "U2") (pin "P$6") (pinfunction "/PG_P$6") (pintype "output"))
    )
    (net (code "51") (name "3.3V") (class "Default")
      (node (ref "C18") (pin "1") (pinfunction "1_1") (pintype "passive"))
      (node (ref "C27") (pin "1") (pinfunction "1_1") (pintype "passive"))
      (node (ref "C28") (pin "1") (pinfunction "1_1") (pintype "passive"))
      (node (ref "C29") (pin "1") (pinfunction "1_1") (pintype "passive"))
      (node (ref "C5") (pin "1") (pinfunction "1_1") (pintype "passive"))
      (node (ref "C6") (pin "1") (pinfunction "1_1") (pintype "passive"))
      (node (ref "C8") (pin "1") (pinfunction "1_1") (pintype "passive"))
      (node (ref "C9") (pin "1") (pinfunction "1_1") (pintype "passive"))
      (node (ref "J1") (pin "1") (pinfunction "VDD_1") (pintype "passive"))
      (node (ref "JP11") (pin "1") (pinfunction "1_1") (pintype "passive"))
      (node (ref "JP2") (pin "21") (pinfunction "21_21") (pintype "passive"))
      (node (ref "JP2") (pin "22") (pinfunction "22_22") (pintype "passive"))
      (node (ref "JP3") (pin "1") (pinfunction "1_1") (pintype "passive"))
      (node (ref "JP3") (pin "2") (pinfunction "2_2") (pintype "passive"))
      (node (ref "JP5") (pin "19") (pinfunction "19_19") (pintype "passive"))
      (node (ref "JP5") (pin "20") (pinfunction "20_20") (pintype "passive"))
      (node (ref "JP6") (pin "1") (pinfunction "1_1") (pintype "passive"))
      (node (ref "JP6") (pin "2") (pinfunction "2_2") (pintype "passive"))
      (node (ref "LED1") (pin "2") (pinfunction "COMMON_ANODE_2") (pintype "passive"))
      (node (ref "LED2") (pin "2") (pinfunction "COMMON_ANODE_2") (pintype "passive"))
      (node (ref "LED3") (pin "A") (pinfunction "A_A") (pintype "passive"))
      (node (ref "R1") (pin "2") (pinfunction "2_2") (pintype "passive"))
      (node (ref "TP3") (pin "P$1") (pinfunction "P$1_P$1") (pintype "bidirectional"))
      (node (ref "U1") (pin "5") (pinfunction "OUT_5") (pintype "passive"))
      (node (ref "U3") (pin "1") (pinfunction "VREFH_1") (pintype "input"))
      (node (ref "U3") (pin "19") (pinfunction "VDD_19") (pintype "power_in"))
      (node (ref "U3") (pin "35") (pinfunction "VBAT2_35") (pintype "power_in"))
      (node (ref "U3") (pin "43") (pinfunction "VBAT1_43") (pintype "power_in"))
      (node (ref "U3") (pin "55") (pinfunction "VDD2_55") (pintype "power_in"))
      (node (ref "U3") (pin "56") (pinfunction "VDDA_56") (pintype "power_in"))
    )
    (net (code "52") (name "GND") (class "Default")
      (node (ref "C1") (pin "2") (pinfunction "2_2") (pintype "passive"))
      (node (ref "C11") (pin "2") (pinfunction "2_2") (pintype "passive"))
      (node (ref "C13") (pin "2") (pinfunction "2_2") (pintype "passive"))
      (node (ref "C14") (pin "2") (pinfunction "2_2") (pintype "passive"))
      (node (ref "C16") (pin "1") (pinfunction "1_1") (pintype "passive"))
      (node (ref "C17") (pin "2") (pinfunction "2_2") (pintype "passive"))
      (node (ref "C18") (pin "2") (pinfunction "2_2") (pintype "passive"))
      (node (ref "C19") (pin "2") (pinfunction "2_2") (pintype "passive"))
      (node (ref "C2") (pin "2") (pinfunction "2_2") (pintype "passive"))
      (node (ref "C20") (pin "2") (pinfunction "2_2") (pintype "passive"))
      (node (ref "C21") (pin "2") (pinfunction "2_2") (pintype "passive"))
      (node (ref "C22") (pin "2") (pinfunction "2_2") (pintype "passive"))
      (node (ref "C23") (pin "2") (pinfunction "2_2") (pintype "passive"))
      (node (ref "C24") (pin "2") (pinfunction "2_2") (pintype "passive"))
      (node (ref "C25") (pin "2") (pinfunction "2_2") (pintype "passive"))
      (node (ref "C26") (pin "2") (pinfunction "2_2") (pintype "passive"))
      (node (ref "C27") (pin "2") (pinfunction "2_2") (pintype "passive"))
      (node (ref "C28") (pin "2") (pinfunction "2_2") (pintype "passive"))
      (node (ref "C29") (pin "2") (pinfunction "2_2") (pintype "passive"))
      (node (ref "C3") (pin "2") (pinfunction "2_2") (pintype "passive"))
      (node (ref "C30") (pin "2") (pinfunction "2_2") (pintype "passive"))
      (node (ref "C31") (pin "2") (pinfunction "2_2") (pintype "passive"))
      (node (ref "C4") (pin "2") (pinfunction "2_2") (pintype "passive"))
      (node (ref "C5") (pin "2") (pinfunction "2_2") (pintype "passive"))
      (node (ref "C6") (pin "2") (pinfunction "2_2") (pintype "passive"))
      (node (ref "C7") (pin "2") (pinfunction "2_2") (pintype "passive"))
      (node (ref "C8") (pin "2") (pinfunction "2_2") (pintype "passive"))
      (node (ref "C9") (pin "2") (pinfunction "2_2") (pintype "passive"))
      (node (ref "CF1") (pin "5") (pinfunction "5_5") (pintype "passive"))
      (node (ref "IC1") (pin "3") (pinfunction "GND_3") (pintype "power_in"))
      (node (ref "IC1") (pin "EXP") (pinfunction "GND_EXP") (pintype "power_in"))
      (node (ref "IC1") (pin "M") (pinfunction "GND_M") (pintype "power_in"))
      (node (ref "J1") (pin "3") (pinfunction "GND3_3") (pintype "passive"))
      (node (ref "J1") (pin "5") (pinfunction "GND5_5") (pintype "passive"))
      (node (ref "J1") (pin "9") (pinfunction "GND9_9") (pintype "passive"))
      (node (ref "JP1") (pin "GND") (pinfunction "1_GND") (pintype "passive"))
      (node (ref "JP10") (pin "2") (pinfunction "2_2") (pintype "passive"))
      (node (ref "JP11") (pin "2") (pinfunction "2_2") (pintype "passive"))
      (node (ref "JP2") (pin "1") (pinfunction "1_1") (pintype "passive"))
      (node (ref "JP2") (pin "2") (pinfunction "2_2") (pintype "passive"))
      (node (ref "JP3") (pin "13") (pinfunction "13_13") (pintype "passive"))
      (node (ref "JP3") (pin "14") (pinfunction "14_14") (pintype "passive"))
      (node (ref "JP5") (pin "1") (pinfunction "1_1") (pintype "passive"))
      (node (ref "JP5") (pin "2") (pinfunction "2_2") (pintype "passive"))
      (node (ref "JP6") (pin "11") (pinfunction "11_11") (pintype "passive"))
      (node (ref "JP6") (pin "12") (pinfunction "12_12") (pintype "passive"))
      (node (ref "JP8") (pin "2") (pinfunction "2_2") (pintype "passive"))
      (node (ref "R14") (pin "2") (pinfunction "2_2") (pintype "passive"))
      (node (ref "R2") (pin "1") (pinfunction "1_1") (pintype "passive"))
      (node (ref "RP1") (pin "1") (pinfunction "1_1") (pintype "passive"))
      (node (ref "RP3") (pin "1") (pinfunction "1_1") (pintype "passive"))
      (node (ref "RT1") (pin "2") (pinfunction "2_2") (pintype "passive"))
      (node (ref "S1") (pin "1") (pinfunction "O_1") (pintype "passive"))
      (node (ref "S2") (pin "B2") (pinfunction "2_B2") (pintype "passive"))
      (node (ref "TP4") (pin "P$1") (pinfunction "P$1_P$1") (pintype "bidirectional"))
      (node (ref "U$2") (pin "GND1") (pinfunction "OUTERCONDUCTOR_GND1") (pintype "bidirectional"))
      (node (ref "U$2") (pin "GND2") (pinfunction "OUTERCONDUCTOR_GND2") (pintype "bidirectional"))
      (node (ref "U$2") (pin "GND3") (pinfunction "OUTERCONDUCTOR_GND3") (pintype "bidirectional"))
      (node (ref "U$2") (pin "GND4") (pinfunction "OUTERCONDUCTOR_GND4") (pintype "bidirectional"))
      (node (ref "U1") (pin "2") (pinfunction "GND_2") (pintype "input"))
      (node (ref "U2") (pin "P$10") (pinfunction "VSS1_P$10") (pintype "power_in"))
      (node (ref "U2") (pin "P$11") (pinfunction "VSS2_P$11") (pintype "power_in"))
      (node (ref "U2") (pin "P$17") (pinfunction "CE_P$17") (pintype "input"))
      (node (ref "U2") (pin "P$21") (pinfunction "THERMAL_P$21") (pintype "power_in"))
      (node (ref "U2") (pin "P$4") (pinfunction "PROG2_P$4") (pintype "input"))
      (node (ref "U3") (pin "2") (pinfunction "VREFL_2") (pintype "input"))
      (node (ref "U3") (pin "20") (pinfunction "VSS2_20") (pintype "power_in"))
      (node (ref "U3") (pin "3") (pinfunction "VSSA_3") (pintype "power_in"))
      (node (ref "U3") (pin "36") (pinfunction "GND/SCAN_36") (pintype "power_in"))
      (node (ref "U3") (pin "38") (pinfunction "GND_PA2_38") (pintype "power_in"))
      (node (ref "U3") (pin "4") (pinfunction "VSS_4") (pintype "power_in"))
      (node (ref "U3") (pin "40") (pinfunction "GND_PA1_40") (pintype "power_in"))
      (node (ref "U3") (pin "PGND1") (pinfunction "GND1_PGND1") (pintype "power_in"))
      (node (ref "U3") (pin "PGND2") (pinfunction "GND2_PGND2") (pintype "power_in"))
    )
    (net (code "53") (name "Net-(C10-Pad1)") (class "Default")
      (node (ref "C10") (pin "1") (pinfunction "1_1") (pintype "passive"))
      (node (ref "C12") (pin "2") (pinfunction "2_2") (pintype "passive"))
      (node (ref "L2") (pin "1") (pinfunction "1_1") (pintype "passive"))
    )
    (net (code "54") (name "Net-(C12-Pad1)") (class "Default")
      (node (ref "C12") (pin "1") (pinfunction "1_1") (pintype "passive"))
      (node (ref "C13") (pin "1") (pinfunction "1_1") (pintype "passive"))
      (node (ref "L2") (pin "2") (pinfunction "2_2") (pintype "passive"))
      (node (ref "L3") (pin "1") (pinfunction "1_1") (pintype "passive"))
    )
    (net (code "55") (name "Net-(C14-Pad1)") (class "Default")
      (node (ref "C14") (pin "1") (pinfunction "1_1") (pintype "passive"))
      (node (ref "C15") (pin "1") (pinfunction "1_1") (pintype "passive"))
      (node (ref "L3") (pin "2") (pinfunction "2_2") (pintype "passive"))
    )
    (net (code "56") (name "Net-(C22-Pad1)") (class "Default")
      (node (ref "C22") (pin "1") (pinfunction "1_1") (pintype "passive"))
      (node (ref "R6") (pin "1") (pinfunction "1_1") (pintype "passive"))
      (node (ref "X1") (pin "2") (pinfunction "2_2") (pintype "passive"))
    )
    (net (code "57") (name "Net-(C30-Pad1)") (class "Default")
      (node (ref "C30") (pin "1") (pinfunction "1_1") (pintype "passive"))
      (node (ref "X2") (pin "1") (pinfunction "1_1") (pintype "passive"))
    )
    (net (code "58") (name "Net-(C31-Pad1)") (class "Default")
      (node (ref "C31") (pin "1") (pinfunction "1_1") (pintype "passive"))
      (node (ref "X2") (pin "2") (pinfunction "2_2") (pintype "passive"))
    )
    (net (code "59") (name "Net-(CF1-Pad4)") (class "Default")
      (node (ref "CF1") (pin "4") (pinfunction "4_4") (pintype "passive"))
      (node (ref "TP12") (pin "P$1") (pinfunction "P$1_P$1") (pintype "bidirectional"))
    )
    (net (code "60") (name "Net-(IC1-CTS)") (class "Default")
      (node (ref "IC1") (pin "23") (pinfunction "CTS_23") (pintype "input"))
      (node (ref "TP18") (pin "P$1") (pinfunction "P$1_P$1") (pintype "bidirectional"))
    )
    (net (code "61") (name "Net-(IC1-DCD)") (class "Default")
      (node (ref "IC1") (pin "1") (pinfunction "DCD_1") (pintype "input"))
      (node (ref "TP16") (pin "P$1") (pinfunction "P$1_P$1") (pintype "bidirectional"))
    )
    (net (code "62") (name "Net-(IC1-DSR)") (class "Default")
      (node (ref "IC1") (pin "27") (pinfunction "DSR_27") (pintype "input"))
      (node (ref "TP17") (pin "P$1") (pinfunction "P$1_P$1") (pintype "bidirectional"))
    )
    (net (code "63") (name "Net-(IC1-DTR)") (class "Default")
      (node (ref "IC1") (pin "28") (pinfunction "DTR_28") (pintype "output"))
      (node (ref "TP9") (pin "P$1") (pinfunction "P$1_P$1") (pintype "bidirectional"))
    )
    (net (code "64") (name "Net-(IC1-RI)") (class "Default")
      (node (ref "IC1") (pin "2") (pinfunction "RI_2") (pintype "input"))
      (node (ref "TP14") (pin "P$1") (pinfunction "P$1_P$1") (pintype "bidirectional"))
    )
    (net (code "65") (name "Net-(IC1-RTS)") (class "Default")
      (node (ref "IC1") (pin "24") (pinfunction "RTS_24") (pintype "output"))
      (node (ref "TP8") (pin "P$1") (pinfunction "P$1_P$1") (pintype "bidirectional"))
    )
    (net (code "66") (name "Net-(IC1-SUSPEND)") (class "Default")
      (node (ref "IC1") (pin "12") (pinfunction "SUSPEND_12") (pintype "output"))
      (node (ref "TP6") (pin "P$1") (pinfunction "P$1_P$1") (pintype "bidirectional"))
    )
    (net (code "67") (name "Net-(IC1-VDD)") (class "Default")
      (node (ref "C19") (pin "1") (pinfunction "1_1") (pintype "passive"))
      (node (ref "C24") (pin "1") (pinfunction "1_1") (pintype "passive"))
      (node (ref "IC1") (pin "6") (pinfunction "VDD_6") (pintype "power_in"))
      (node (ref "R13") (pin "1") (pinfunction "1_1") (pintype "passive"))
      (node (ref "TP13") (pin "P$1") (pinfunction "P$1_P$1") (pintype "bidirectional"))
    )
    (net (code "68") (name "Net-(IC1-~{RST})") (class "Default")
      (node (ref "IC1") (pin "9") (pinfunction "~{RST}_9") (pintype "bidirectional"))
      (node (ref "JP8") (pin "1") (pinfunction "1_1") (pintype "passive"))
      (node (ref "R13") (pin "2") (pinfunction "2_2") (pintype "passive"))
    )
    (net (code "69") (name "Net-(IC1-~{SUSPEND})") (class "Default")
      (node (ref "IC1") (pin "11") (pinfunction "~{SUSPEND}_11") (pintype "output"))
      (node (ref "TP7") (pin "P$1") (pinfunction "P$1_P$1") (pintype "bidirectional"))
    )
    (net (code "70") (name "Net-(JP5-Pad13)") (class "Default")
      (node (ref "JP5") (pin "13") (pinfunction "13_13") (pintype "passive"))
      (node (ref "JP5") (pin "14") (pinfunction "14_14") (pintype "passive"))
      (node (ref "R11") (pin "1") (pinfunction "1_1") (pintype "passive"))
    )
    (net (code "71") (name "Net-(JP6-Pad10)") (class "Default")
      (node (ref "JP6") (pin "10") (pinfunction "10_10") (pintype "passive"))
      (node (ref "JP6") (pin "9") (pinfunction "9_9") (pintype "passive"))
      (node (ref "R10") (pin "1") (pinfunction "1_1") (pintype "passive"))
    )
    (net (code "72") (name "Net-(LED1-BK)") (class "Default")
      (node (ref "LED1") (pin "1") (pinfunction "BK_1") (pintype "passive"))
      (node (ref "R5") (pin "2") (pinfunction "2_2") (pintype "passive"))
    )
    (net (code "73") (name "Net-(LED1-GK)") (class "Default")
      (node (ref "LED1") (pin "4") (pinfunction "GK_4") (pintype "passive"))
      (node (ref "R4") (pin "2") (pinfunction "2_2") (pintype "passive"))
    )
    (net (code "74") (name "Net-(LED1-RK)") (class "Default")
      (node (ref "LED1") (pin "3") (pinfunction "RK_3") (pintype "passive"))
      (node (ref "R3") (pin "2") (pinfunction "2_2") (pintype "passive"))
    )
    (net (code "75") (name "Net-(LED2-BK)") (class "Default")
      (node (ref "LED2") (pin "1") (pinfunction "BK_1") (pintype "passive"))
      (node (ref "R9") (pin "1") (pinfunction "1_1") (pintype "passive"))
    )
    (net (code "76") (name "Net-(LED2-GK)") (class "Default")
      (node (ref "LED2") (pin "4") (pinfunction "GK_4") (pintype "passive"))
      (node (ref "R8") (pin "1") (pinfunction "1_1") (pintype "passive"))
    )
    (net (code "77") (name "Net-(LED2-RK)") (class "Default")
      (node (ref "LED2") (pin "3") (pinfunction "RK_3") (pintype "passive"))
      (node (ref "R7") (pin "1") (pinfunction "1_1") (pintype "passive"))
    )
    (net (code "78") (name "Net-(LED3-PadK)") (class "Default")
      (node (ref "LED3") (pin "K") (pinfunction "K_K") (pintype "passive"))
      (node (ref "R2") (pin "2") (pinfunction "2_2") (pintype "passive"))
    )
    (net (code "79") (name "Net-(S1-P)") (class "Default")
      (node (ref "S1") (pin "2") (pinfunction "P_2") (pintype "passive"))
      (node (ref "U1") (pin "3") (pinfunction "EN_3") (pintype "input"))
    )
    (net (code "80") (name "Net-(U$2-CENTERCONDUCTOR)") (class "Default")
      (node (ref "C15") (pin "2") (pinfunction "2_2") (pintype "passive"))
      (node (ref "U$2") (pin "P$3") (pinfunction "CENTERCONDUCTOR_P$3") (pintype "bidirectional"))
    )
    (net (code "81") (name "Net-(U1-BP)") (class "Default")
      (node (ref "C7") (pin "1") (pinfunction "1_1") (pintype "passive"))
      (node (ref "U1") (pin "4") (pinfunction "BP_4") (pintype "input"))
    )
    (net (code "82") (name "Net-(U2-PROG1)") (class "Default")
      (node (ref "RP1") (pin "2") (pinfunction "2_2") (pintype "passive"))
      (node (ref "U2") (pin "P$13") (pinfunction "PROG1_P$13") (pintype "passive"))
    )
    (net (code "83") (name "Net-(U2-PROG3)") (class "Default")
      (node (ref "RP3") (pin "2") (pinfunction "2_2") (pintype "passive"))
      (node (ref "U2") (pin "P$12") (pinfunction "PROG3_P$12") (pintype "passive"))
    )
    (net (code "84") (name "Net-(U2-THERM)") (class "Default")
      (node (ref "RT1") (pin "1") (pinfunction "1_1") (pintype "passive"))
      (node (ref "U2") (pin "P$5") (pinfunction "THERM_P$5") (pintype "passive"))
    )
    (net (code "85") (name "Net-(U3-PA_BOOST)") (class "Default")
      (node (ref "TP10") (pin "P$1") (pinfunction "P$1_P$1") (pintype "bidirectional"))
      (node (ref "U3") (pin "41") (pinfunction "PA_BOOST_41") (pintype "output"))
    )
    (net (code "86") (name "Net-(U3-RXTX)") (class "Default")
      (node (ref "TP11") (pin "P$1") (pinfunction "P$1_P$1") (pintype "bidirectional"))
      (node (ref "U3") (pin "37") (pinfunction "RXTX_37") (pintype "output"))
    )
    (net (code "87") (name "Net-(U3-VR_ANA)") (class "Default")
      (node (ref "C25") (pin "1") (pinfunction "1_1") (pintype "passive"))
      (node (ref "U3") (pin "44") (pinfunction "VR_ANA_44") (pintype "output"))
    )
    (net (code "88") (name "Net-(U3-VR_DIG)") (class "Default")
      (node (ref "C23") (pin "1") (pinfunction "1_1") (pintype "passive"))
      (node (ref "U3") (pin "45") (pinfunction "VR_DIG_45") (pintype "output"))
    )
    (net (code "89") (name "V+") (class "Default")
      (node (ref "C4") (pin "1") (pinfunction "1_1") (pintype "passive"))
      (node (ref "JP1") (pin "VCC") (pinfunction "2_VCC") (pintype "passive"))
      (node (ref "JP10") (pin "1") (pinfunction "1_1") (pintype "passive"))
      (node (ref "TP1") (pin "P$1") (pinfunction "P$1_P$1") (pintype "bidirectional"))
      (node (ref "U2") (pin "P$14") (pinfunction "VBAT1_P$14") (pintype "power_in"))
      (node (ref "U2") (pin "P$15") (pinfunction "VBAT2_P$15") (pintype "power_in"))
      (node (ref "U2") (pin "P$16") (pinfunction "VBATSENS_P$16") (pintype "passive"))
    )
    (net (code "90") (name "unconnected-(J1-RTCK-Pad7)") (class "Default")
      (node (ref "J1") (pin "7") (pinfunction "RTCK_7") (pintype "passive"))
    )
    (net (code "91") (name "unconnected-(J1-TDI-Pad8)") (class "Default")
      (node (ref "J1") (pin "8") (pinfunction "TDI_8") (pintype "passive"))
    )
    (net (code "92") (name "unconnected-(J1-TDO-Pad6)") (class "Default")
      (node (ref "J1") (pin "6") (pinfunction "TDO_6") (pintype "passive"))
    )
    (net (code "93") (name "unconnected-(U3-NC-Pad30)") (class "Default")
      (node (ref "U3") (pin "30") (pinfunction "NC_30") (pintype "no_connect"))
    )
  )
)
